# scheda_cpu.net
KiCad netlist of a schematic drawn in EAGLE
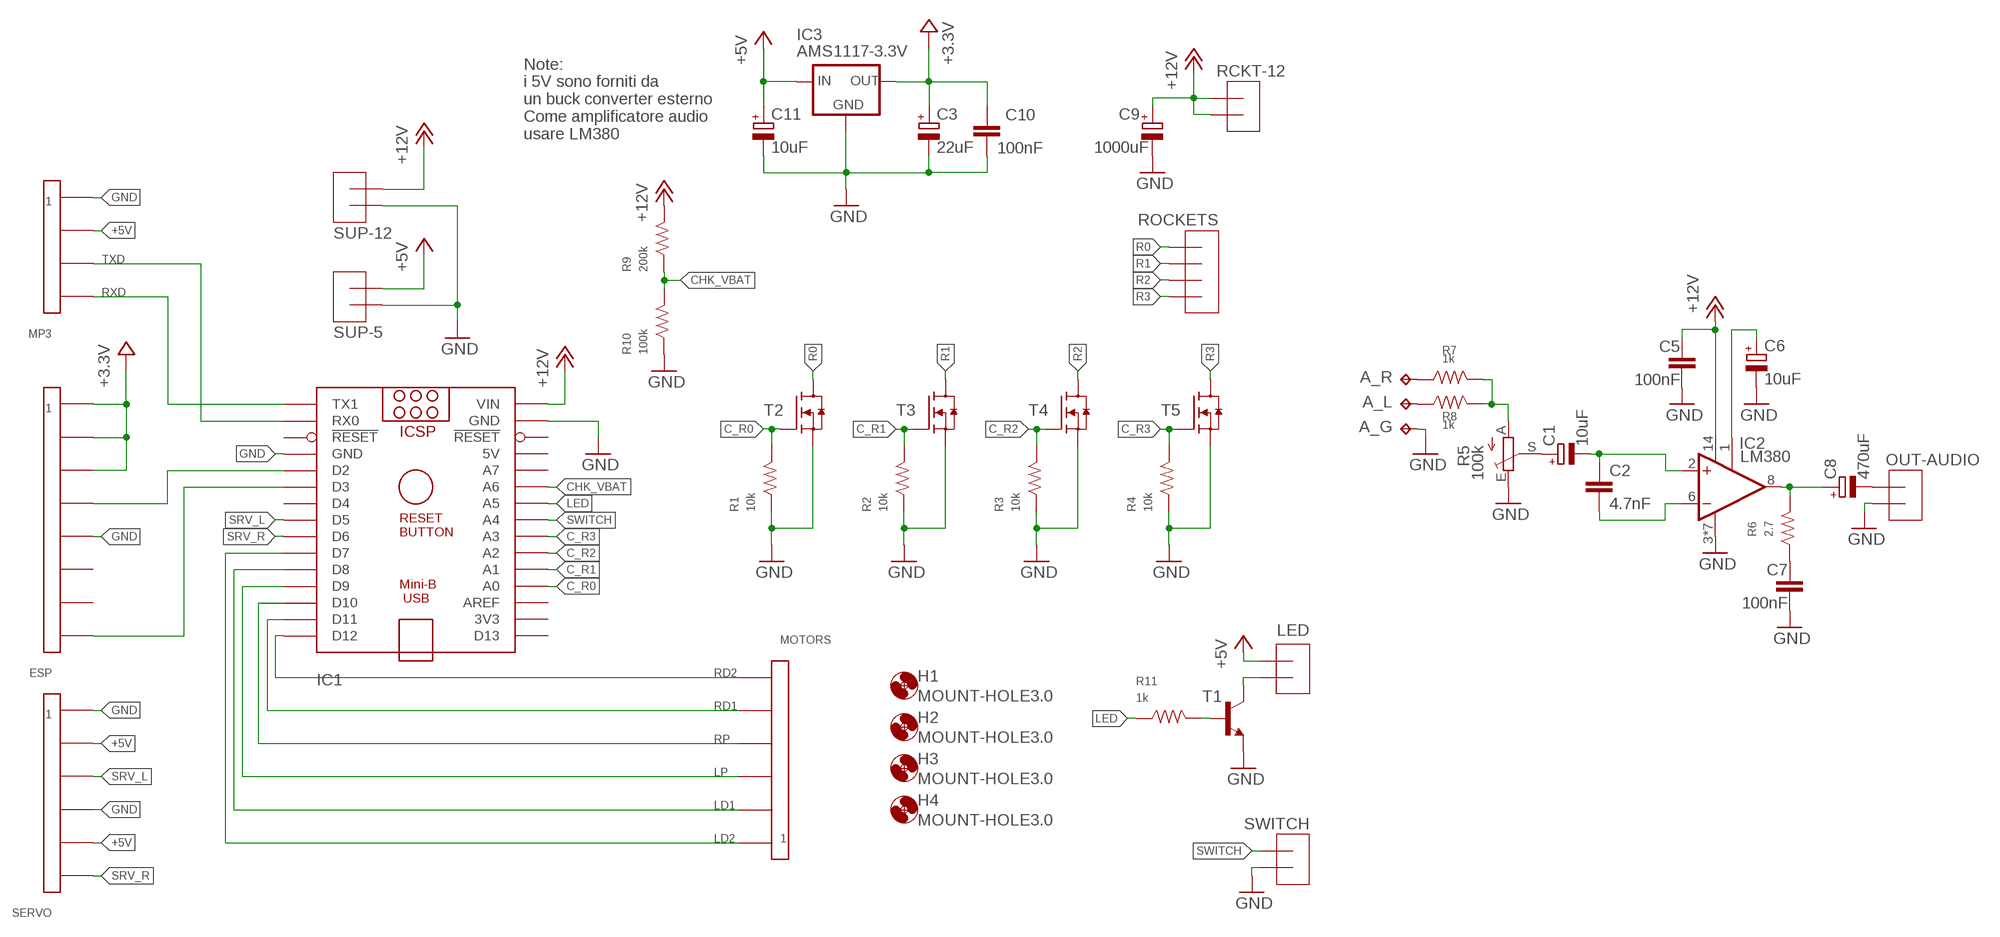
[diagram p0: schematic, sheet 1]

(export (version "E")
  (design (tool "Eeschema 10.0.6"))
  (components
    (comp (ref "A_G")
      (value "TPTP15SQ")
      (footprint "eagle-import:TP15SQ")
      (libsource (lib "eagle-import") (part "TPTP15SQ"))
    )
    (comp (ref "A_L")
      (value "TPTP15SQ")
      (footprint "eagle-import:TP15SQ")
      (libsource (lib "eagle-import") (part "TPTP15SQ"))
    )
    (comp (ref "A_R")
      (value "TPTP15SQ")
      (footprint "eagle-import:TP15SQ")
      (libsource (lib "eagle-import") (part "TPTP15SQ"))
    )
    (comp (ref "C1")
      (value "10uF")
      (footprint "eagle-import:E2-4")
      (libsource (lib "eagle-import") (part "CPOL-EUE2-4"))
    )
    (comp (ref "C2")
      (value "4.7nF")
      (footprint "eagle-import:C1206")
      (libsource (lib "eagle-import") (part "C-EUC1206"))
    )
    (comp (ref "C3")
      (value "22uF")
      (footprint "eagle-import:E2-4")
      (libsource (lib "eagle-import") (part "CPOL-EUE2-4"))
    )
    (comp (ref "C5")
      (value "100nF")
      (footprint "eagle-import:C1206")
      (libsource (lib "eagle-import") (part "C-EUC1206"))
    )
    (comp (ref "C6")
      (value "10uF")
      (footprint "eagle-import:E2-4")
      (libsource (lib "eagle-import") (part "CPOL-EUE2-4"))
    )
    (comp (ref "C7")
      (value "100nF")
      (footprint "eagle-import:C1206")
      (libsource (lib "eagle-import") (part "C-EUC1206"))
    )
    (comp (ref "C8")
      (value "470uF")
      (footprint "eagle-import:E3,5-8")
      (libsource (lib "eagle-import") (part "CPOL-EUE3.5-8"))
    )
    (comp (ref "C9")
      (value "1000uF")
      (footprint "eagle-import:E3,5-10")
      (libsource (lib "eagle-import") (part "CPOL-EUE3.5-10"))
    )
    (comp (ref "C10")
      (value "100nF")
      (footprint "eagle-import:C1206")
      (libsource (lib "eagle-import") (part "C-EUC1206"))
    )
    (comp (ref "C11")
      (value "10uF")
      (footprint "eagle-import:E2-4")
      (libsource (lib "eagle-import") (part "CPOL-EUE2-4"))
    )
    (comp (ref "ESP")
      (value "CONNECTOR-82X4-CONNECTOR")
      (footprint "eagle-import:2X4-CONNECTOR")
      (libsource (lib "eagle-import") (part "CONNECTOR-82X4-CONNECTOR"))
    )
    (comp (ref "H1")
      (value "MOUNT-HOLE3.0")
      (footprint "eagle-import:3,0")
      (libsource (lib "eagle-import") (part "MOUNT-HOLE3.0"))
    )
    (comp (ref "H2")
      (value "MOUNT-HOLE3.0")
      (footprint "eagle-import:3,0")
      (libsource (lib "eagle-import") (part "MOUNT-HOLE3.0"))
    )
    (comp (ref "H3")
      (value "MOUNT-HOLE3.0")
      (footprint "eagle-import:3,0")
      (libsource (lib "eagle-import") (part "MOUNT-HOLE3.0"))
    )
    (comp (ref "H4")
      (value "MOUNT-HOLE3.0")
      (footprint "eagle-import:3,0")
      (libsource (lib "eagle-import") (part "MOUNT-HOLE3.0"))
    )
    (comp (ref "IC1")
      (value "ARDUINO-NANO")
      (footprint "eagle-import:ARDUINO_NANO")
      (libsource (lib "eagle-import") (part "ARDUINO-NANO"))
    )
    (comp (ref "IC2")
      (value "LM380")
      (footprint "eagle-import:DIL14")
      (libsource (lib "eagle-import") (part "LM380"))
    )
    (comp (ref "IC3")
      (value "AMS1117-3.3V")
      (footprint "eagle-import:SOT223")
      (fields (field (name "MPN") "REG1117"))
      (libsource (lib "eagle-import") (part "AMS1117"))
    )
    (comp (ref "LED")
      (value "MORSETTIERE-2")
      (footprint "eagle-import:MORSETTIERE-2")
      (libsource (lib "eagle-import") (part "MORSETTIERE-2"))
    )
    (comp (ref "MOTORS")
      (value "CONNECTOR-6")
      (footprint "eagle-import:1X6-CONNECTOR")
      (libsource (lib "eagle-import") (part "CONNECTOR-6"))
    )
    (comp (ref "MP3")
      (value "CONNECTOR-4")
      (footprint "eagle-import:1X4-CONNECTOR")
      (libsource (lib "eagle-import") (part "CONNECTOR-4"))
    )
    (comp (ref "OUT-AUDIO")
      (value "MORSETTIERE-2")
      (footprint "eagle-import:MORSETTIERE-2")
      (libsource (lib "eagle-import") (part "MORSETTIERE-2"))
    )
    (comp (ref "R1")
      (value "10k")
      (footprint "eagle-import:1206-RESISTOR")
      (libsource (lib "eagle-import") (part "RESISTOR1206"))
    )
    (comp (ref "R2")
      (value "10k")
      (footprint "eagle-import:1206-RESISTOR")
      (libsource (lib "eagle-import") (part "RESISTOR1206"))
    )
    (comp (ref "R3")
      (value "10k")
      (footprint "eagle-import:1206-RESISTOR")
      (libsource (lib "eagle-import") (part "RESISTOR1206"))
    )
    (comp (ref "R4")
      (value "10k")
      (footprint "eagle-import:1206-RESISTOR")
      (libsource (lib "eagle-import") (part "RESISTOR1206"))
    )
    (comp (ref "R5")
      (value "100k")
      (footprint "eagle-import:S64W")
      (libsource (lib "eagle-import") (part "TRIM_EU-S64W"))
    )
    (comp (ref "R6")
      (value "2.7")
      (footprint "eagle-import:1206-RESISTOR")
      (libsource (lib "eagle-import") (part "RESISTOR1206"))
    )
    (comp (ref "R7")
      (value "1k")
      (footprint "eagle-import:1206-RESISTOR")
      (libsource (lib "eagle-import") (part "RESISTOR1206"))
    )
    (comp (ref "R8")
      (value "1k")
      (footprint "eagle-import:1206-RESISTOR")
      (libsource (lib "eagle-import") (part "RESISTOR1206"))
    )
    (comp (ref "R9")
      (value "200k")
      (footprint "eagle-import:1206-RESISTOR")
      (libsource (lib "eagle-import") (part "RESISTOR1206"))
    )
    (comp (ref "R10")
      (value "100k")
      (footprint "eagle-import:1206-RESISTOR")
      (libsource (lib "eagle-import") (part "RESISTOR1206"))
    )
    (comp (ref "R11")
      (value "1k")
      (footprint "eagle-import:1206-RESISTOR")
      (libsource (lib "eagle-import") (part "RESISTOR1206"))
    )
    (comp (ref "RCKT-12")
      (value "MORSETTIERE-2")
      (footprint "eagle-import:MORSETTIERE-2")
      (libsource (lib "eagle-import") (part "MORSETTIERE-2"))
    )
    (comp (ref "ROCKETS")
      (value "MORSETTIERE-4")
      (footprint "eagle-import:MORSETTIERE-4")
      (libsource (lib "eagle-import") (part "MORSETTIERE-4"))
    )
    (comp (ref "SERVO")
      (value "CONNECTOR-6")
      (footprint "eagle-import:1X6-CONNECTOR")
      (libsource (lib "eagle-import") (part "CONNECTOR-6"))
    )
    (comp (ref "SUP-5")
      (value "MORSETTIERE-2")
      (footprint "eagle-import:MORSETTIERE-2")
      (libsource (lib "eagle-import") (part "MORSETTIERE-2"))
    )
    (comp (ref "SUP-12")
      (value "MORSETTIERE-2")
      (footprint "eagle-import:MORSETTIERE-2")
      (libsource (lib "eagle-import") (part "MORSETTIERE-2"))
    )
    (comp (ref "SWITCH")
      (value "MORSETTIERE-2")
      (footprint "eagle-import:MORSETTIERE-2")
      (libsource (lib "eagle-import") (part "MORSETTIERE-2"))
    )
    (comp (ref "T1")
      (value "BC-817")
      (footprint "eagle-import:SOT-23")
      (libsource (lib "eagle-import") (part "BC-817"))
    )
    (comp (ref "T2")
      (value "MCU80N03A")
      (footprint "eagle-import:D-PAK_TO252AA")
      (libsource (lib "eagle-import") (part "MCU80N03A"))
    )
    (comp (ref "T3")
      (value "MCU80N03A")
      (footprint "eagle-import:D-PAK_TO252AA")
      (libsource (lib "eagle-import") (part "MCU80N03A"))
    )
    (comp (ref "T4")
      (value "MCU80N03A")
      (footprint "eagle-import:D-PAK_TO252AA")
      (libsource (lib "eagle-import") (part "MCU80N03A"))
    )
    (comp (ref "T5")
      (value "MCU80N03A")
      (footprint "eagle-import:D-PAK_TO252AA")
      (libsource (lib "eagle-import") (part "MCU80N03A"))
    )
  )
  (nets
    (net (code "1") (name "+3.3V") (class "Default")
      (node (ref "C10") (pin "1") (pinfunction "1_1") (pintype "passive"))
      (node (ref "C3") (pin "+") (pinfunction "+_+") (pintype "passive"))
      (node (ref "ESP") (pin "P$1") (pinfunction "P$1_P$1") (pintype "bidirectional"))
      (node (ref "ESP") (pin "P$2") (pinfunction "P$2_P$2") (pintype "bidirectional"))
      (node (ref "ESP") (pin "P$3") (pinfunction "P$3_P$3") (pintype "bidirectional"))
      (node (ref "IC3") (pin "2") (pinfunction "OUT_2") (pintype "passive"))
    )
    (net (code "2") (name "+5V") (class "Default")
      (node (ref "C11") (pin "+") (pinfunction "+_+") (pintype "passive"))
      (node (ref "IC3") (pin "3") (pinfunction "IN_3") (pintype "input"))
      (node (ref "LED") (pin "A") (pinfunction "A_A") (pintype "bidirectional"))
      (node (ref "MP3") (pin "P$2") (pinfunction "P$2_P$2") (pintype "bidirectional"))
      (node (ref "SERVO") (pin "P$2") (pinfunction "P$2_P$2") (pintype "bidirectional"))
      (node (ref "SERVO") (pin "P$5") (pinfunction "P$5_P$5") (pintype "bidirectional"))
      (node (ref "SUP-5") (pin "A") (pinfunction "A_A") (pintype "bidirectional"))
    )
    (net (code "3") (name "+12V") (class "Default")
      (node (ref "C5") (pin "1") (pinfunction "1_1") (pintype "passive"))
      (node (ref "C9") (pin "+") (pinfunction "+_+") (pintype "passive"))
      (node (ref "IC1") (pin "15") (pinfunction "VIN_15") (pintype "power_in"))
      (node (ref "IC2") (pin "14") (pinfunction "VSS_14") (pintype "power_in"))
      (node (ref "R9") (pin "P$2") (pinfunction "P$2_P$2") (pintype "bidirectional"))
      (node (ref "RCKT-12") (pin "A") (pinfunction "A_A") (pintype "bidirectional"))
      (node (ref "RCKT-12") (pin "B") (pinfunction "B_B") (pintype "bidirectional"))
      (node (ref "SUP-12") (pin "A") (pinfunction "A_A") (pintype "bidirectional"))
    )
    (net (code "4") (name "/5V") (class "Default")
      (node (ref "IC1") (pin "12") (pinfunction "5V_12") (pintype "power_in"))
    )
    (net (code "5") (name "/LD1") (class "Default")
      (node (ref "IC1") (pin "26") (pinfunction "D8_26") (pintype "bidirectional"))
      (node (ref "MOTORS") (pin "P$2") (pinfunction "P$2_P$2") (pintype "bidirectional"))
    )
    (net (code "6") (name "/LD2") (class "Default")
      (node (ref "IC1") (pin "25") (pinfunction "D7_25") (pintype "bidirectional"))
      (node (ref "MOTORS") (pin "P$1") (pinfunction "P$1_P$1") (pintype "bidirectional"))
    )
    (net (code "7") (name "/LP") (class "Default")
      (node (ref "IC1") (pin "27") (pinfunction "D9_27") (pintype "bidirectional"))
      (node (ref "MOTORS") (pin "P$3") (pinfunction "P$3_P$3") (pintype "bidirectional"))
    )
    (net (code "8") (name "/RD1") (class "Default")
      (node (ref "IC1") (pin "29") (pinfunction "D11_29") (pintype "bidirectional"))
      (node (ref "MOTORS") (pin "P$5") (pinfunction "P$5_P$5") (pintype "bidirectional"))
    )
    (net (code "9") (name "/RD2") (class "Default")
      (node (ref "IC1") (pin "30") (pinfunction "D12_30") (pintype "bidirectional"))
      (node (ref "MOTORS") (pin "P$6") (pinfunction "P$6_P$6") (pintype "bidirectional"))
    )
    (net (code "10") (name "/RP") (class "Default")
      (node (ref "IC1") (pin "28") (pinfunction "D10_28") (pintype "bidirectional"))
      (node (ref "MOTORS") (pin "P$4") (pinfunction "P$4_P$4") (pintype "bidirectional"))
    )
    (net (code "11") (name "/RXD") (class "Default")
      (node (ref "IC1") (pin "16") (pinfunction "TX1_16") (pintype "bidirectional"))
      (node (ref "MP3") (pin "P$4") (pinfunction "P$4_P$4") (pintype "bidirectional"))
    )
    (net (code "12") (name "/TXD") (class "Default")
      (node (ref "IC1") (pin "17") (pinfunction "RX0_17") (pintype "bidirectional"))
      (node (ref "MP3") (pin "P$3") (pinfunction "P$3_P$3") (pintype "bidirectional"))
    )
    (net (code "13") (name "CHK_VBAT") (class "Default")
      (node (ref "IC1") (pin "10") (pinfunction "A6_10") (pintype "bidirectional"))
      (node (ref "R10") (pin "P$2") (pinfunction "P$2_P$2") (pintype "bidirectional"))
      (node (ref "R9") (pin "P$1") (pinfunction "P$1_P$1") (pintype "bidirectional"))
    )
    (net (code "14") (name "C_R0") (class "Default")
      (node (ref "IC1") (pin "4") (pinfunction "A0_4") (pintype "bidirectional"))
      (node (ref "R1") (pin "P$2") (pinfunction "P$2_P$2") (pintype "bidirectional"))
      (node (ref "T2") (pin "1") (pinfunction "G_1") (pintype "passive"))
    )
    (net (code "15") (name "C_R1") (class "Default")
      (node (ref "IC1") (pin "5") (pinfunction "A1_5") (pintype "bidirectional"))
      (node (ref "R2") (pin "P$2") (pinfunction "P$2_P$2") (pintype "bidirectional"))
      (node (ref "T3") (pin "1") (pinfunction "G_1") (pintype "passive"))
    )
    (net (code "16") (name "C_R2") (class "Default")
      (node (ref "IC1") (pin "6") (pinfunction "A2_6") (pintype "bidirectional"))
      (node (ref "R3") (pin "P$2") (pinfunction "P$2_P$2") (pintype "bidirectional"))
      (node (ref "T4") (pin "1") (pinfunction "G_1") (pintype "passive"))
    )
    (net (code "17") (name "C_R3") (class "Default")
      (node (ref "IC1") (pin "7") (pinfunction "A3_7") (pintype "bidirectional"))
      (node (ref "R4") (pin "P$2") (pinfunction "P$2_P$2") (pintype "bidirectional"))
      (node (ref "T5") (pin "1") (pinfunction "G_1") (pintype "passive"))
    )
    (net (code "18") (name "GND") (class "Default")
      (node (ref "A_G") (pin "TP") (pinfunction "TP_TP") (pintype "input"))
      (node (ref "C10") (pin "2") (pinfunction "2_2") (pintype "passive"))
      (node (ref "C11") (pin "-") (pinfunction "-_-") (pintype "passive"))
      (node (ref "C3") (pin "-") (pinfunction "-_-") (pintype "passive"))
      (node (ref "C5") (pin "2") (pinfunction "2_2") (pintype "passive"))
      (node (ref "C6") (pin "-") (pinfunction "-_-") (pintype "passive"))
      (node (ref "C7") (pin "2") (pinfunction "2_2") (pintype "passive"))
      (node (ref "C9") (pin "-") (pinfunction "-_-") (pintype "passive"))
      (node (ref "ESP") (pin "P$5") (pinfunction "P$5_P$5") (pintype "bidirectional"))
      (node (ref "IC1") (pin "14") (pinfunction "GND_14") (pintype "power_in"))
      (node (ref "IC1") (pin "19") (pinfunction "GND_19") (pintype "power_in"))
      (node (ref "IC2") (pin "10") (pinfunction "GND_10") (pintype "power_in"))
      (node (ref "IC2") (pin "11") (pinfunction "GND_11") (pintype "power_in"))
      (node (ref "IC2") (pin "12") (pinfunction "GND_12") (pintype "power_in"))
      (node (ref "IC2") (pin "3") (pinfunction "GND_3") (pintype "power_in"))
      (node (ref "IC2") (pin "4") (pinfunction "GND_4") (pintype "power_in"))
      (node (ref "IC2") (pin "5") (pinfunction "GND_5") (pintype "power_in"))
      (node (ref "IC2") (pin "7") (pinfunction "GND_7") (pintype "power_in"))
      (node (ref "IC3") (pin "1") (pinfunction "GND_1") (pintype "input"))
      (node (ref "MP3") (pin "P$1") (pinfunction "P$1_P$1") (pintype "bidirectional"))
      (node (ref "OUT-AUDIO") (pin "A") (pinfunction "A_A") (pintype "bidirectional"))
      (node (ref "R1") (pin "P$1") (pinfunction "P$1_P$1") (pintype "bidirectional"))
      (node (ref "R10") (pin "P$1") (pinfunction "P$1_P$1") (pintype "bidirectional"))
      (node (ref "R2") (pin "P$1") (pinfunction "P$1_P$1") (pintype "bidirectional"))
      (node (ref "R3") (pin "P$1") (pinfunction "P$1_P$1") (pintype "bidirectional"))
      (node (ref "R4") (pin "P$1") (pinfunction "P$1_P$1") (pintype "bidirectional"))
      (node (ref "R5") (pin "E") (pinfunction "E_E") (pintype "passive"))
      (node (ref "SERVO") (pin "P$1") (pinfunction "P$1_P$1") (pintype "bidirectional"))
      (node (ref "SERVO") (pin "P$4") (pinfunction "P$4_P$4") (pintype "bidirectional"))
      (node (ref "SUP-12") (pin "B") (pinfunction "B_B") (pintype "bidirectional"))
      (node (ref "SUP-5") (pin "B") (pinfunction "B_B") (pintype "bidirectional"))
      (node (ref "SWITCH") (pin "A") (pinfunction "A_A") (pintype "bidirectional"))
      (node (ref "T1") (pin "P$1") (pinfunction "E_P$1") (pintype "passive"))
      (node (ref "T2") (pin "3") (pinfunction "S_3") (pintype "passive"))
      (node (ref "T3") (pin "3") (pinfunction "S_3") (pintype "passive"))
      (node (ref "T4") (pin "3") (pinfunction "S_3") (pintype "passive"))
      (node (ref "T5") (pin "3") (pinfunction "S_3") (pintype "passive"))
    )
    (net (code "19") (name "LED") (class "Default")
      (node (ref "IC1") (pin "9") (pinfunction "A5_9") (pintype "bidirectional"))
      (node (ref "R11") (pin "P$1") (pinfunction "P$1_P$1") (pintype "bidirectional"))
    )
    (net (code "20") (name "Net-(A_L-PadTP)") (class "Default")
      (node (ref "A_L") (pin "TP") (pinfunction "TP_TP") (pintype "input"))
      (node (ref "R8") (pin "P$1") (pinfunction "P$1_P$1") (pintype "bidirectional"))
    )
    (net (code "21") (name "Net-(A_R-PadTP)") (class "Default")
      (node (ref "A_R") (pin "TP") (pinfunction "TP_TP") (pintype "input"))
      (node (ref "R7") (pin "P$1") (pinfunction "P$1_P$1") (pintype "bidirectional"))
    )
    (net (code "22") (name "Net-(C1-Pad+)") (class "Default")
      (node (ref "C1") (pin "+") (pinfunction "+_+") (pintype "passive"))
      (node (ref "R5") (pin "S") (pinfunction "S_S") (pintype "passive"))
    )
    (net (code "23") (name "Net-(C7-Pad1)") (class "Default")
      (node (ref "C7") (pin "1") (pinfunction "1_1") (pintype "passive"))
      (node (ref "R6") (pin "P$1") (pinfunction "P$1_P$1") (pintype "bidirectional"))
    )
    (net (code "24") (name "Net-(C8-Pad-)") (class "Default")
      (node (ref "C8") (pin "-") (pinfunction "-_-") (pintype "passive"))
      (node (ref "OUT-AUDIO") (pin "B") (pinfunction "B_B") (pintype "bidirectional"))
    )
    (net (code "25") (name "Net-(IC1-D2)") (class "Default")
      (node (ref "ESP") (pin "P$4") (pinfunction "P$4_P$4") (pintype "bidirectional"))
      (node (ref "IC1") (pin "20") (pinfunction "D2_20") (pintype "bidirectional"))
    )
    (net (code "26") (name "Net-(IC1-D3)") (class "Default")
      (node (ref "ESP") (pin "P$8") (pinfunction "P$8_P$8") (pintype "bidirectional"))
      (node (ref "IC1") (pin "21") (pinfunction "D3_21") (pintype "bidirectional"))
    )
    (net (code "27") (name "Net-(IC2-+IN)") (class "Default")
      (node (ref "C1") (pin "-") (pinfunction "-_-") (pintype "passive"))
      (node (ref "C2") (pin "1") (pinfunction "1_1") (pintype "passive"))
      (node (ref "IC2") (pin "2") (pinfunction "+IN_2") (pintype "input"))
    )
    (net (code "28") (name "Net-(IC2--IN)") (class "Default")
      (node (ref "C2") (pin "2") (pinfunction "2_2") (pintype "passive"))
      (node (ref "IC2") (pin "6") (pinfunction "-IN_6") (pintype "input"))
    )
    (net (code "29") (name "Net-(IC2-BYPASS)") (class "Default")
      (node (ref "C6") (pin "+") (pinfunction "+_+") (pintype "passive"))
      (node (ref "IC2") (pin "1") (pinfunction "BYPASS_1") (pintype "passive"))
    )
    (net (code "30") (name "Net-(IC2-OUT)") (class "Default")
      (node (ref "C8") (pin "+") (pinfunction "+_+") (pintype "passive"))
      (node (ref "IC2") (pin "8") (pinfunction "OUT_8") (pintype "output"))
      (node (ref "R6") (pin "P$2") (pinfunction "P$2_P$2") (pintype "bidirectional"))
    )
    (net (code "31") (name "Net-(R5-PadA)") (class "Default")
      (node (ref "R5") (pin "A") (pinfunction "A_A") (pintype "passive"))
      (node (ref "R7") (pin "P$2") (pinfunction "P$2_P$2") (pintype "bidirectional"))
      (node (ref "R8") (pin "P$2") (pinfunction "P$2_P$2") (pintype "bidirectional"))
    )
    (net (code "32") (name "Net-(T1-B)") (class "Default")
      (node (ref "R11") (pin "P$2") (pinfunction "P$2_P$2") (pintype "bidirectional"))
      (node (ref "T1") (pin "P$2") (pinfunction "B_P$2") (pintype "passive"))
    )
    (net (code "33") (name "Net-(T1-C)") (class "Default")
      (node (ref "LED") (pin "B") (pinfunction "B_B") (pintype "bidirectional"))
      (node (ref "T1") (pin "P$3") (pinfunction "C_P$3") (pintype "passive"))
    )
    (net (code "34") (name "R0") (class "Default")
      (node (ref "ROCKETS") (pin "D") (pinfunction "D_D") (pintype "bidirectional"))
      (node (ref "T2") (pin "4") (pinfunction "D_4") (pintype "passive"))
    )
    (net (code "35") (name "R1") (class "Default")
      (node (ref "ROCKETS") (pin "C") (pinfunction "C_C") (pintype "bidirectional"))
      (node (ref "T3") (pin "4") (pinfunction "D_4") (pintype "passive"))
    )
    (net (code "36") (name "R2") (class "Default")
      (node (ref "ROCKETS") (pin "B") (pinfunction "B_B") (pintype "bidirectional"))
      (node (ref "T4") (pin "4") (pinfunction "D_4") (pintype "passive"))
    )
    (net (code "37") (name "R3") (class "Default")
      (node (ref "ROCKETS") (pin "A") (pinfunction "A_A") (pintype "bidirectional"))
      (node (ref "T5") (pin "4") (pinfunction "D_4") (pintype "passive"))
    )
    (net (code "38") (name "SRV_L") (class "Default")
      (node (ref "IC1") (pin "23") (pinfunction "D5_23") (pintype "bidirectional"))
      (node (ref "SERVO") (pin "P$3") (pinfunction "P$3_P$3") (pintype "bidirectional"))
    )
    (net (code "39") (name "SRV_R") (class "Default")
      (node (ref "IC1") (pin "24") (pinfunction "D6_24") (pintype "bidirectional"))
      (node (ref "SERVO") (pin "P$6") (pinfunction "P$6_P$6") (pintype "bidirectional"))
    )
    (net (code "40") (name "SWITCH") (class "Default")
      (node (ref "IC1") (pin "8") (pinfunction "A4_8") (pintype "bidirectional"))
      (node (ref "SWITCH") (pin "B") (pinfunction "B_B") (pintype "bidirectional"))
    )
    (net (code "41") (name "unconnected-(ESP-PadP$6)") (class "Default")
      (node (ref "ESP") (pin "P$6") (pinfunction "P$6_P$6") (pintype "bidirectional"))
    )
    (net (code "42") (name "unconnected-(ESP-PadP$7)") (class "Default")
      (node (ref "ESP") (pin "P$7") (pinfunction "P$7_P$7") (pintype "bidirectional"))
    )
    (net (code "43") (name "unconnected-(IC1-3V3-Pad2)") (class "Default")
      (node (ref "IC1") (pin "2") (pinfunction "3V3_2") (pintype "output"))
    )
    (net (code "44") (name "unconnected-(IC1-A7-Pad11)") (class "Default")
      (node (ref "IC1") (pin "11") (pinfunction "A7_11") (pintype "bidirectional"))
    )
    (net (code "45") (name "unconnected-(IC1-AREF-Pad3)") (class "Default")
      (node (ref "IC1") (pin "3") (pinfunction "AREF_3") (pintype "input"))
    )
    (net (code "46") (name "unconnected-(IC1-D4-Pad22)") (class "Default")
      (node (ref "IC1") (pin "22") (pinfunction "D4_22") (pintype "bidirectional"))
    )
    (net (code "47") (name "unconnected-(IC1-D13-Pad1)") (class "Default")
      (node (ref "IC1") (pin "1") (pinfunction "D13_1") (pintype "bidirectional"))
    )
    (net (code "48") (name "unconnected-(IC1-~{RESET}-Pad13)") (class "Default")
      (node (ref "IC1") (pin "13") (pinfunction "~{RESET}_13") (pintype "input"))
    )
    (net (code "49") (name "unconnected-(IC1-~{RESET}-Pad18)") (class "Default")
      (node (ref "IC1") (pin "18") (pinfunction "~{RESET}_18") (pintype "input"))
    )
  )
)
